# LPC800_TSSOP_breadboard_mini.net
KiCad netlist of a schematic drawn in EAGLE
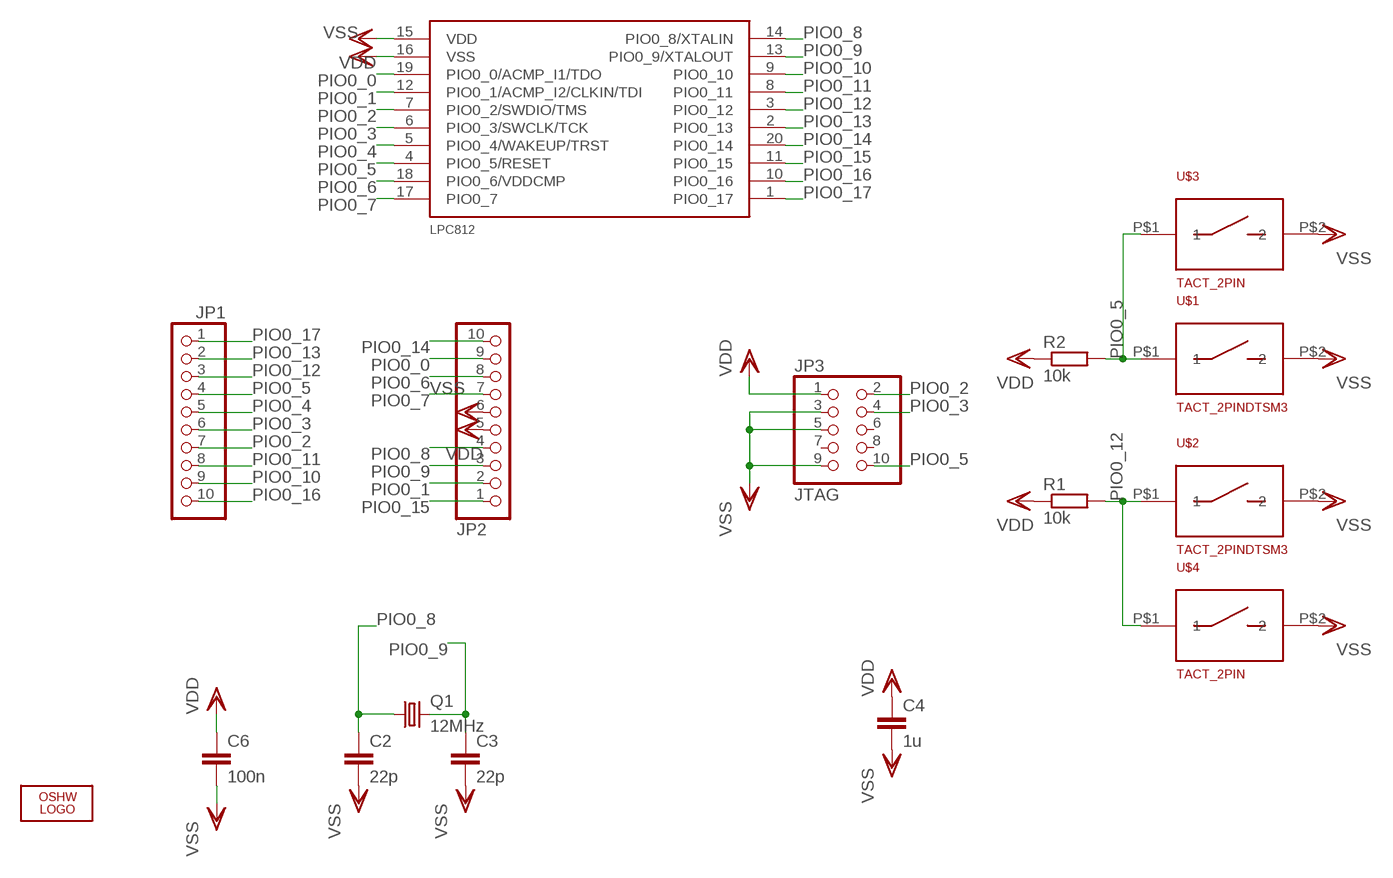
[diagram p0: schematic, sheet 1]

(export (version "E")
  (design (tool "Eeschema 10.0.6"))
  (components
    (comp (ref "C2")
      (value "22p")
      (footprint "eagle-import:C0603K")
      (libsource (lib "eagle-import") (part "C-EUC0603K"))
    )
    (comp (ref "C3")
      (value "22p")
      (footprint "eagle-import:C0603K")
      (libsource (lib "eagle-import") (part "C-EUC0603K"))
    )
    (comp (ref "C4")
      (value "1u")
      (footprint "eagle-import:C0805K")
      (libsource (lib "eagle-import") (part "bart_rcl_C-EUC0805K"))
    )
    (comp (ref "C6")
      (value "100n")
      (footprint "eagle-import:C0603K")
      (libsource (lib "eagle-import") (part "C-EUC0603K"))
    )
    (comp (ref "JP1")
      (value "PINHD-1X10NORM_OCT")
      (footprint "eagle-import:1X10_NORMAL_OCT")
      (libsource (lib "eagle-import") (part "PINHD-1X10NORM_OCT"))
    )
    (comp (ref "JP2")
      (value "PINHD-1X10NORM_OCT")
      (footprint "eagle-import:1X10_NORMAL_OCT")
      (libsource (lib "eagle-import") (part "PINHD-1X10NORM_OCT"))
    )
    (comp (ref "JP3")
      (value "JTAG")
      (footprint "eagle-import:2X05_1.27_SMD")
      (libsource (lib "eagle-import") (part "PINHD-2X5SMD_1.27_SMD"))
    )
    (comp (ref "LOGO2")
      (value "OSHW_LOGO_FILLX0150-NT")
      (footprint "eagle-import:OSHW_FILLX150_NOTEXT")
      (libsource (lib "eagle-import") (part "OSHW_LOGO_FILLX0150-NT"))
    )
    (comp (ref "LPC812")
      (value "LPC812M101JDH20")
      (footprint "eagle-import:TSSOP20")
      (libsource (lib "eagle-import") (part "LPC812M101JDH20"))
    )
    (comp (ref "Q1")
      (value "12MHz")
      (footprint "eagle-import:CRYSTAL_5.0X3.2")
      (libsource (lib "eagle-import") (part "CRYSTALSMD_5.0X3.2"))
    )
    (comp (ref "R1")
      (value "10k")
      (footprint "eagle-import:R0603")
      (libsource (lib "eagle-import") (part "R-EU_R0603"))
    )
    (comp (ref "R2")
      (value "10k")
      (footprint "eagle-import:R0603")
      (libsource (lib "eagle-import") (part "R-EU_R0603"))
    )
    (comp (ref "U$1")
      (value "TACT_2PINDTSM3")
      (footprint "eagle-import:DTSM3")
      (libsource (lib "eagle-import") (part "TACT_2PINDTSM3"))
    )
    (comp (ref "U$2")
      (value "TACT_2PINDTSM3")
      (footprint "eagle-import:DTSM3")
      (libsource (lib "eagle-import") (part "TACT_2PINDTSM3"))
    )
    (comp (ref "U$3")
      (value "TACT_2PIN")
      (footprint "eagle-import:TD-85XU")
      (libsource (lib "eagle-import") (part "TACT_2PIN"))
    )
    (comp (ref "U$4")
      (value "TACT_2PIN")
      (footprint "eagle-import:TD-85XU")
      (libsource (lib "eagle-import") (part "TACT_2PIN"))
    )
  )
  (nets
    (net (code "1") (name "/PIO0_0") (class "Default")
      (node (ref "JP2") (pin "9") (pinfunction "9_9") (pintype "passive"))
      (node (ref "LPC812") (pin "19") (pinfunction "PIO0_0/ACMP_I1/TDO_19") (pintype "bidirectional"))
    )
    (net (code "2") (name "/PIO0_1") (class "Default")
      (node (ref "JP2") (pin "2") (pinfunction "2_2") (pintype "passive"))
      (node (ref "LPC812") (pin "12") (pinfunction "PIO0_1/ACMP_I2/CLKIN/TDI_12") (pintype "bidirectional"))
    )
    (net (code "3") (name "/PIO0_2") (class "Default")
      (node (ref "JP1") (pin "7") (pinfunction "7_7") (pintype "passive"))
      (node (ref "JP3") (pin "2") (pinfunction "2_2") (pintype "passive"))
      (node (ref "LPC812") (pin "7") (pinfunction "PIO0_2/SWDIO/TMS_7") (pintype "bidirectional"))
    )
    (net (code "4") (name "/PIO0_3") (class "Default")
      (node (ref "JP1") (pin "6") (pinfunction "6_6") (pintype "passive"))
      (node (ref "JP3") (pin "4") (pinfunction "4_4") (pintype "passive"))
      (node (ref "LPC812") (pin "6") (pinfunction "PIO0_3/SWCLK/TCK_6") (pintype "bidirectional"))
    )
    (net (code "5") (name "/PIO0_4") (class "Default")
      (node (ref "JP1") (pin "5") (pinfunction "5_5") (pintype "passive"))
      (node (ref "LPC812") (pin "5") (pinfunction "PIO0_4/WAKEUP/TRST_5") (pintype "bidirectional"))
    )
    (net (code "6") (name "/PIO0_5") (class "Default")
      (node (ref "JP1") (pin "4") (pinfunction "4_4") (pintype "passive"))
      (node (ref "JP3") (pin "10") (pinfunction "10_10") (pintype "passive"))
      (node (ref "LPC812") (pin "4") (pinfunction "PIO0_5/RESET_4") (pintype "bidirectional"))
      (node (ref "R2") (pin "2") (pinfunction "2_2") (pintype "passive"))
      (node (ref "U$1") (pin "P$1") (pinfunction "1_P$1") (pintype "bidirectional"))
      (node (ref "U$3") (pin "P$1") (pinfunction "1_P$1") (pintype "bidirectional"))
    )
    (net (code "7") (name "/PIO0_6") (class "Default")
      (node (ref "JP2") (pin "8") (pinfunction "8_8") (pintype "passive"))
      (node (ref "LPC812") (pin "18") (pinfunction "PIO0_6/VDDCMP_18") (pintype "bidirectional"))
    )
    (net (code "8") (name "/PIO0_7") (class "Default")
      (node (ref "JP2") (pin "7") (pinfunction "7_7") (pintype "passive"))
      (node (ref "LPC812") (pin "17") (pinfunction "PIO0_7_17") (pintype "bidirectional"))
    )
    (net (code "9") (name "/PIO0_8") (class "Default")
      (node (ref "C2") (pin "1") (pinfunction "1_1") (pintype "passive"))
      (node (ref "JP2") (pin "4") (pinfunction "4_4") (pintype "passive"))
      (node (ref "LPC812") (pin "14") (pinfunction "PIO0_8/XTALIN_14") (pintype "bidirectional"))
      (node (ref "Q1") (pin "1") (pinfunction "1_1") (pintype "passive"))
    )
    (net (code "10") (name "/PIO0_9") (class "Default")
      (node (ref "C3") (pin "1") (pinfunction "1_1") (pintype "passive"))
      (node (ref "JP2") (pin "3") (pinfunction "3_3") (pintype "passive"))
      (node (ref "LPC812") (pin "13") (pinfunction "PIO0_9/XTALOUT_13") (pintype "bidirectional"))
      (node (ref "Q1") (pin "2") (pinfunction "2_2") (pintype "passive"))
    )
    (net (code "11") (name "/PIO0_10") (class "Default")
      (node (ref "JP1") (pin "9") (pinfunction "9_9") (pintype "passive"))
      (node (ref "LPC812") (pin "9") (pinfunction "PIO0_10_9") (pintype "bidirectional"))
    )
    (net (code "12") (name "/PIO0_11") (class "Default")
      (node (ref "JP1") (pin "8") (pinfunction "8_8") (pintype "passive"))
      (node (ref "LPC812") (pin "8") (pinfunction "PIO0_11_8") (pintype "bidirectional"))
    )
    (net (code "13") (name "/PIO0_12") (class "Default")
      (node (ref "JP1") (pin "3") (pinfunction "3_3") (pintype "passive"))
      (node (ref "LPC812") (pin "3") (pinfunction "PIO0_12_3") (pintype "bidirectional"))
      (node (ref "R1") (pin "2") (pinfunction "2_2") (pintype "passive"))
      (node (ref "U$2") (pin "P$1") (pinfunction "1_P$1") (pintype "bidirectional"))
      (node (ref "U$4") (pin "P$1") (pinfunction "1_P$1") (pintype "bidirectional"))
    )
    (net (code "14") (name "/PIO0_13") (class "Default")
      (node (ref "JP1") (pin "2") (pinfunction "2_2") (pintype "passive"))
      (node (ref "LPC812") (pin "2") (pinfunction "PIO0_13_2") (pintype "bidirectional"))
    )
    (net (code "15") (name "/PIO0_14") (class "Default")
      (node (ref "JP2") (pin "10") (pinfunction "10_10") (pintype "passive"))
      (node (ref "LPC812") (pin "20") (pinfunction "PIO0_14_20") (pintype "bidirectional"))
    )
    (net (code "16") (name "/PIO0_15") (class "Default")
      (node (ref "JP2") (pin "1") (pinfunction "1_1") (pintype "passive"))
      (node (ref "LPC812") (pin "11") (pinfunction "PIO0_15_11") (pintype "bidirectional"))
    )
    (net (code "17") (name "/PIO0_16") (class "Default")
      (node (ref "JP1") (pin "10") (pinfunction "10_10") (pintype "passive"))
      (node (ref "LPC812") (pin "10") (pinfunction "PIO0_16_10") (pintype "bidirectional"))
    )
    (net (code "18") (name "/PIO0_17") (class "Default")
      (node (ref "JP1") (pin "1") (pinfunction "1_1") (pintype "passive"))
      (node (ref "LPC812") (pin "1") (pinfunction "PIO0_17_1") (pintype "bidirectional"))
    )
    (net (code "19") (name "VDD") (class "Default")
      (node (ref "C4") (pin "1") (pinfunction "1_1") (pintype "passive"))
      (node (ref "C6") (pin "1") (pinfunction "1_1") (pintype "passive"))
      (node (ref "JP2") (pin "5") (pinfunction "5_5") (pintype "passive"))
      (node (ref "JP3") (pin "1") (pinfunction "1_1") (pintype "passive"))
      (node (ref "LPC812") (pin "15") (pinfunction "VDD_15") (pintype "bidirectional"))
      (node (ref "R1") (pin "1") (pinfunction "1_1") (pintype "passive"))
      (node (ref "R2") (pin "1") (pinfunction "1_1") (pintype "passive"))
    )
    (net (code "20") (name "VSS") (class "Default")
      (node (ref "C2") (pin "2") (pinfunction "2_2") (pintype "passive"))
      (node (ref "C3") (pin "2") (pinfunction "2_2") (pintype "passive"))
      (node (ref "C4") (pin "2") (pinfunction "2_2") (pintype "passive"))
      (node (ref "C6") (pin "2") (pinfunction "2_2") (pintype "passive"))
      (node (ref "JP2") (pin "6") (pinfunction "6_6") (pintype "passive"))
      (node (ref "JP3") (pin "3") (pinfunction "3_3") (pintype "passive"))
      (node (ref "JP3") (pin "5") (pinfunction "5_5") (pintype "passive"))
      (node (ref "JP3") (pin "9") (pinfunction "9_9") (pintype "passive"))
      (node (ref "LPC812") (pin "16") (pinfunction "VSS_16") (pintype "bidirectional"))
      (node (ref "U$1") (pin "P$2") (pinfunction "2_P$2") (pintype "bidirectional"))
      (node (ref "U$2") (pin "P$2") (pinfunction "2_P$2") (pintype "bidirectional"))
      (node (ref "U$3") (pin "P$2") (pinfunction "2_P$2") (pintype "bidirectional"))
      (node (ref "U$4") (pin "P$2") (pinfunction "2_P$2") (pintype "bidirectional"))
    )
    (net (code "21") (name "unconnected-(JP3-Pad6)") (class "Default")
      (node (ref "JP3") (pin "6") (pinfunction "6_6") (pintype "passive"))
    )
    (net (code "22") (name "unconnected-(JP3-Pad7)") (class "Default")
      (node (ref "JP3") (pin "7") (pinfunction "7_7") (pintype "passive"))
    )
    (net (code "23") (name "unconnected-(JP3-Pad8)") (class "Default")
      (node (ref "JP3") (pin "8") (pinfunction "8_8") (pintype "passive"))
    )
  )
)
